# design.net
KiCad netlist of a schematic drawn in Altium Designer
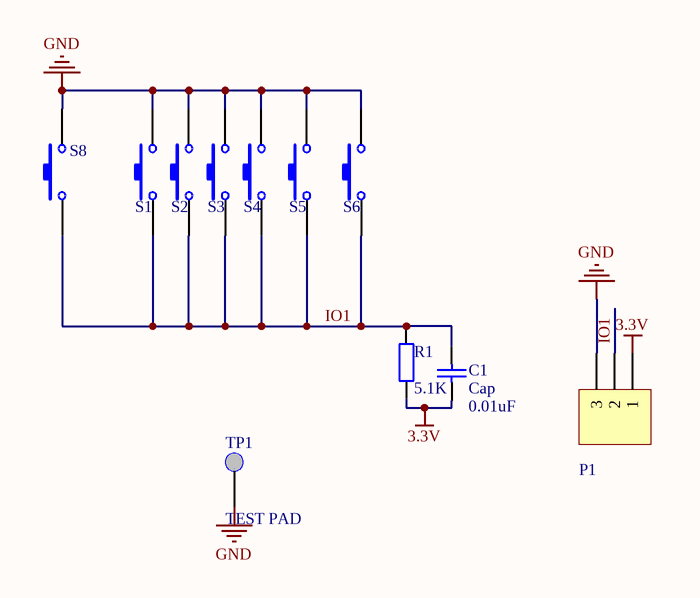
[diagram p0: 起跑.SchDoc]

(export (version "E")
  (design (tool "Eeschema 10.0.6"))
  (components
    (comp (ref "C1")
      (value "Cap")
      (footprint "C2012")
      (description "Capacitor")
      (fields (field (name "ALTIUM_VALUE") "0.01uF") (field (name "PUBLISHER") "Altium Limited"))
      (libsource (lib "Miscellaneous Devices") (part "Cap"))
    )
    (comp (ref "P1")
      (value "Header 3")
      (footprint "HDR1X3")
      (description "Header, 3-Pin")
      (fields (field (name "PUBLISHER") "Altium Limited"))
      (libsource (lib "Sparks") (part "Header 3"))
    )
    (comp (ref "R1")
      (value "5.1K")
      (footprint "R2012")
      (description "Resistor")
      (fields (field (name "Comment") "Res2") (field (name "PUBLISHER") "Altium Limited"))
      (libsource (lib "Miscellaneous Devices") (part "Res2"))
    )
    (comp (ref "S1")
      (value "SW-PB")
      (footprint "AXIAL-0.9")
      (description "Switch")
      (fields (field (name "PUBLISHER") "Altium Limited"))
      (libsource (lib "Miscellaneous Devices") (part "SW-PB"))
    )
    (comp (ref "S2")
      (value "SW-PB")
      (footprint "AXIAL-0.9")
      (description "Switch")
      (fields (field (name "PUBLISHER") "Altium Limited"))
      (libsource (lib "Miscellaneous Devices") (part "SW-PB"))
    )
    (comp (ref "S3")
      (value "SW-PB")
      (footprint "AXIAL-0.9")
      (description "Switch")
      (fields (field (name "PUBLISHER") "Altium Limited"))
      (libsource (lib "Miscellaneous Devices") (part "SW-PB"))
    )
    (comp (ref "S4")
      (value "SW-PB")
      (footprint "AXIAL-0.9")
      (description "Switch")
      (fields (field (name "PUBLISHER") "Altium Limited"))
      (libsource (lib "Miscellaneous Devices") (part "SW-PB"))
    )
    (comp (ref "S5")
      (value "SW-PB")
      (footprint "AXIAL-0.9")
      (description "Switch")
      (fields (field (name "PUBLISHER") "Altium Limited"))
      (libsource (lib "Miscellaneous Devices") (part "SW-PB"))
    )
    (comp (ref "S6")
      (value "SW-PB")
      (footprint "AXIAL-0.9")
      (description "Switch")
      (fields (field (name "PUBLISHER") "Altium Limited"))
      (libsource (lib "Miscellaneous Devices") (part "SW-PB"))
    )
    (comp (ref "S8")
      (value "SW-PB")
      (footprint "AXIAL-0.9")
      (description "Switch")
      (fields (field (name "PUBLISHER") "Altium Limited"))
      (libsource (lib "Miscellaneous Devices") (part "SW-PB"))
    )
    (comp (ref "TP1") (value "TEST PAD") (footprint "PIN") (libsource (lib "刘爽") (part "TEST PAD")))
  )
  (nets
    (net (code "1") (name "/IO1") (class "Default")
      (node (ref "C1") (pin "2") (pinfunction "2_2") (pintype "passive"))
      (node (ref "P1") (pin "2") (pinfunction "2_2") (pintype "passive"))
      (node (ref "R1") (pin "2") (pinfunction "2_2") (pintype "passive"))
      (node (ref "S1") (pin "1") (pinfunction "1_1") (pintype "passive"))
      (node (ref "S2") (pin "1") (pinfunction "1_1") (pintype "passive"))
      (node (ref "S3") (pin "1") (pinfunction "1_1") (pintype "passive"))
      (node (ref "S4") (pin "1") (pinfunction "1_1") (pintype "passive"))
      (node (ref "S5") (pin "1") (pinfunction "1_1") (pintype "passive"))
      (node (ref "S6") (pin "1") (pinfunction "1_1") (pintype "passive"))
      (node (ref "S8") (pin "1") (pinfunction "1_1") (pintype "passive"))
    )
    (net (code "2") (name "3.3V") (class "Default")
      (node (ref "C1") (pin "1") (pinfunction "1_1") (pintype "passive"))
      (node (ref "P1") (pin "1") (pinfunction "1_1") (pintype "passive"))
      (node (ref "R1") (pin "1") (pinfunction "1_1") (pintype "passive"))
    )
    (net (code "3") (name "GND") (class "Default")
      (node (ref "P1") (pin "3") (pinfunction "3_3") (pintype "passive"))
      (node (ref "S1") (pin "2") (pinfunction "2_2") (pintype "passive"))
      (node (ref "S2") (pin "2") (pinfunction "2_2") (pintype "passive"))
      (node (ref "S3") (pin "2") (pinfunction "2_2") (pintype "passive"))
      (node (ref "S4") (pin "2") (pinfunction "2_2") (pintype "passive"))
      (node (ref "S5") (pin "2") (pinfunction "2_2") (pintype "passive"))
      (node (ref "S6") (pin "2") (pinfunction "2_2") (pintype "passive"))
      (node (ref "S8") (pin "2") (pinfunction "2_2") (pintype "passive"))
      (node (ref "TP1") (pin "1") (pinfunction "1_1") (pintype "passive"))
    )
  )
)
